# CH32V307VCT6.net
KiCad netlist of a schematic drawn in EasyEDA Pro
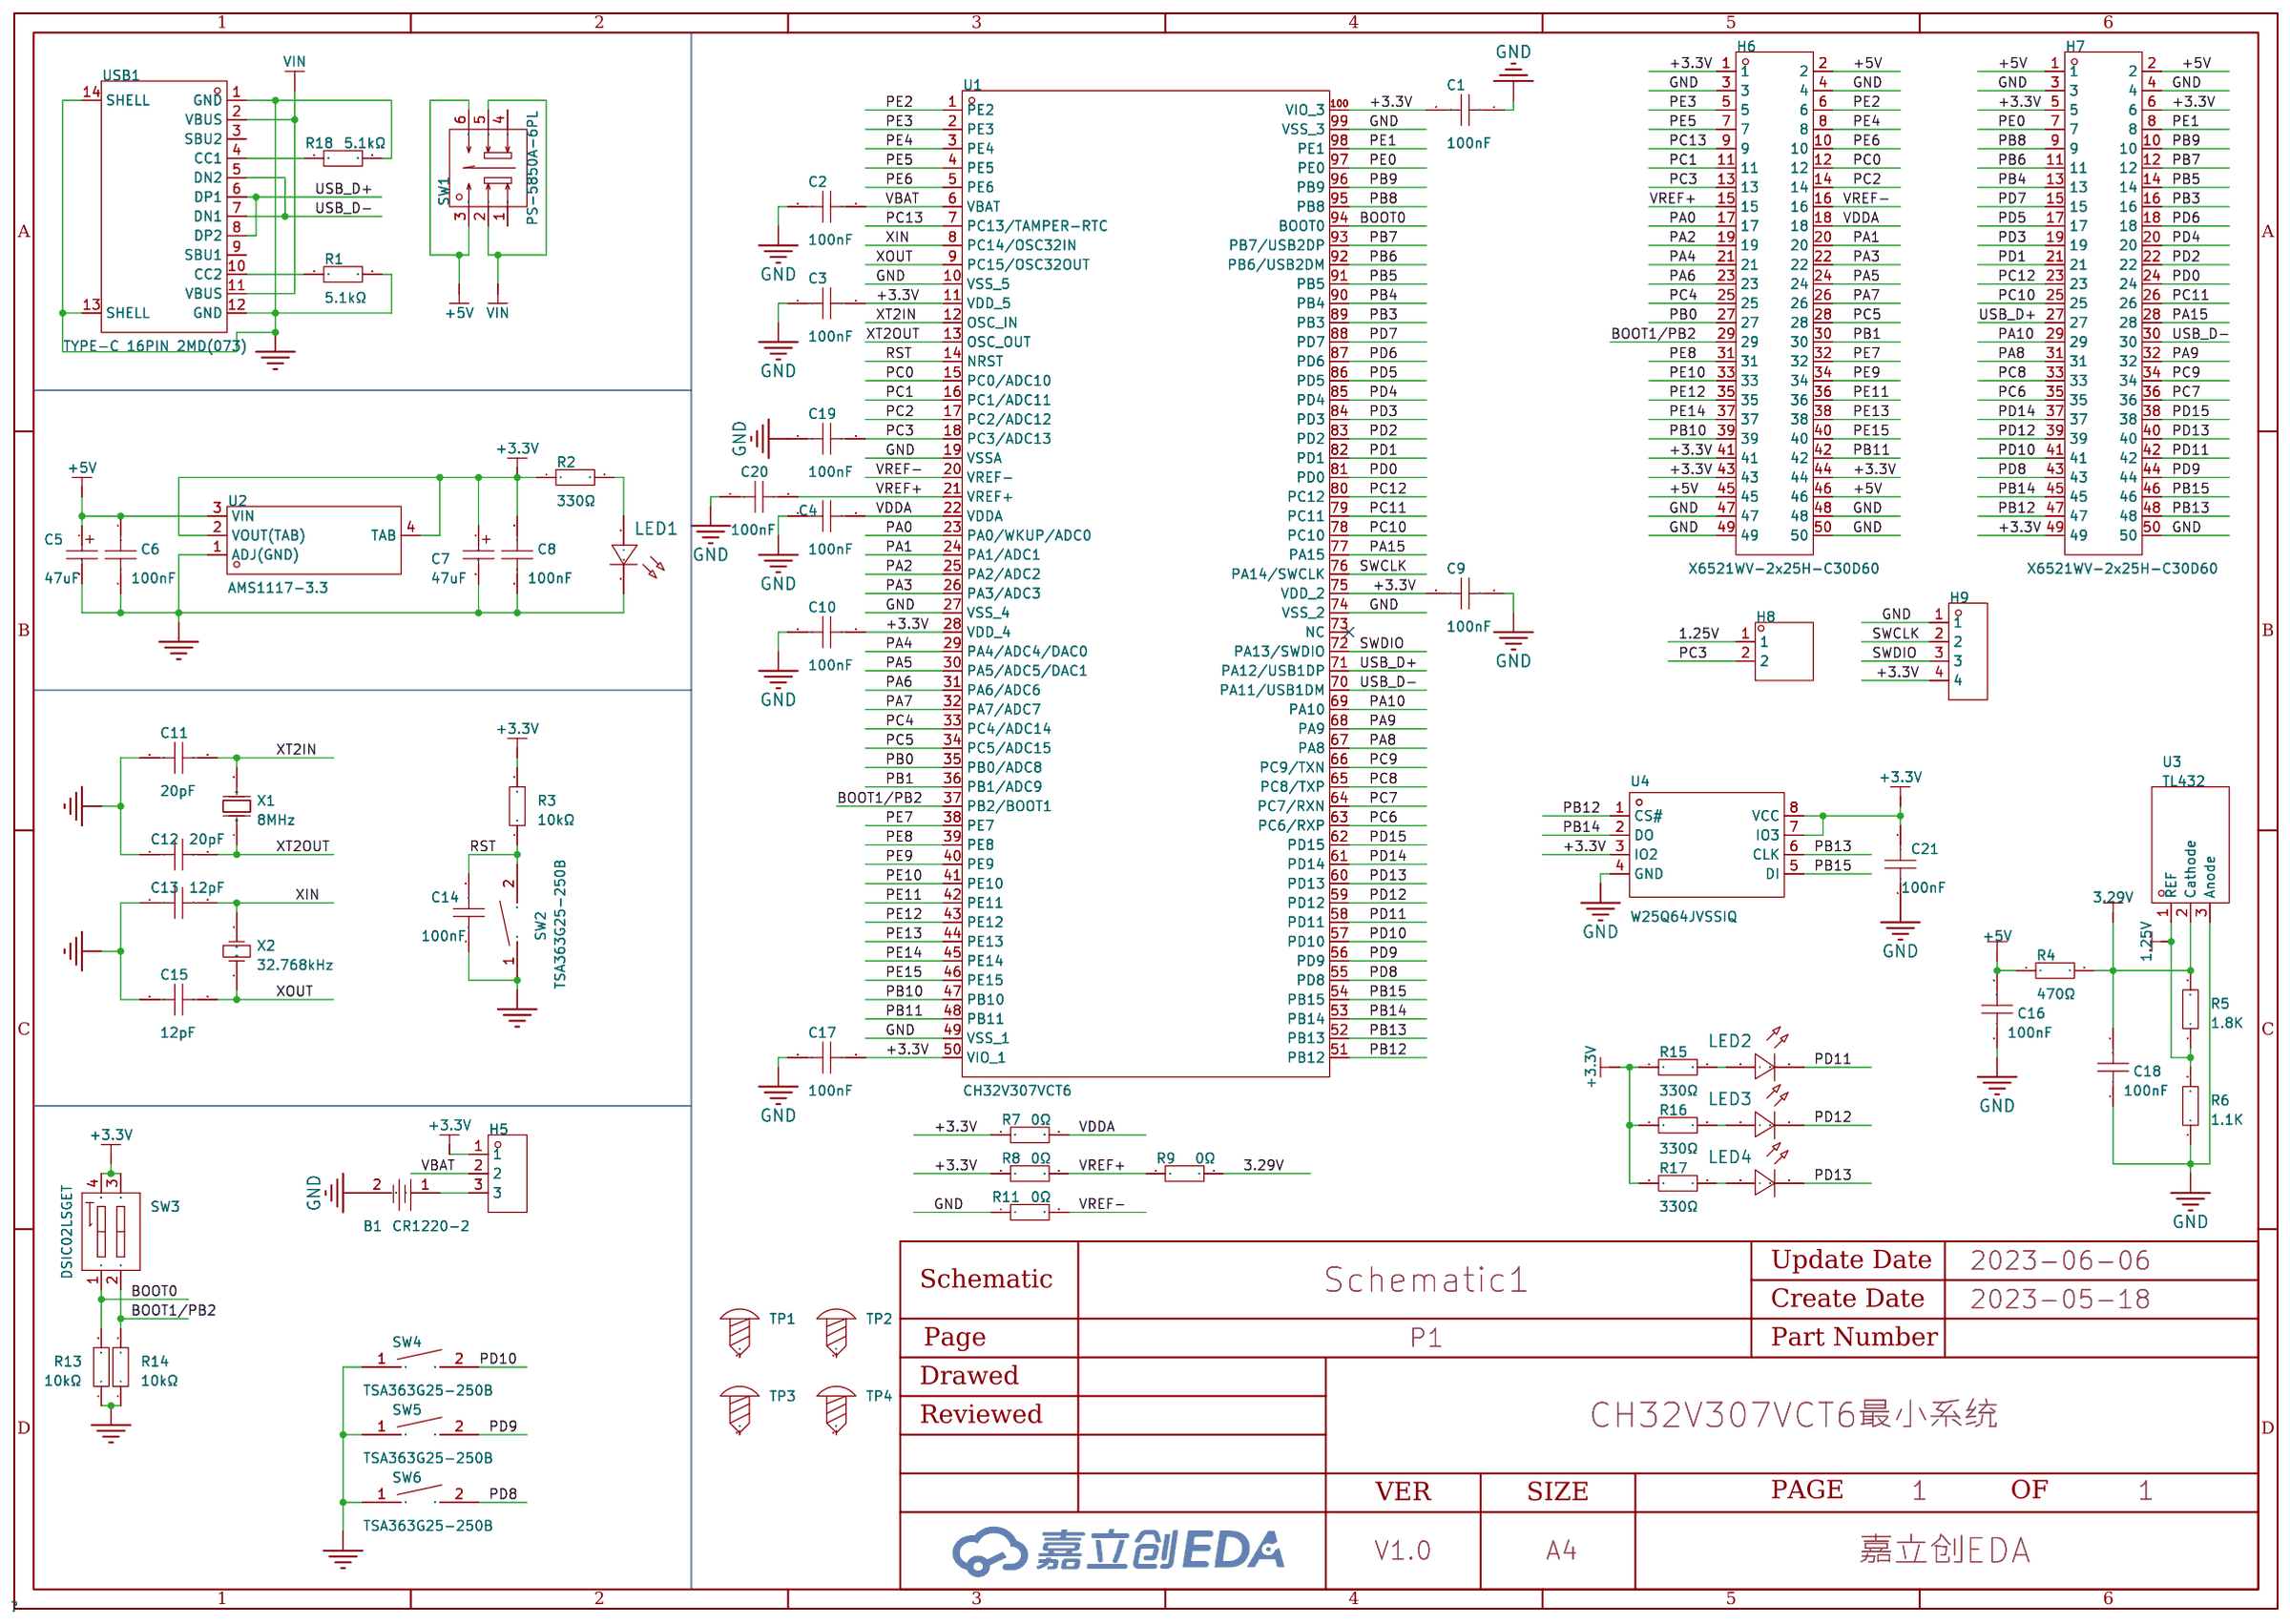
[diagram p0: schematic sheet]

(export (version "E")
  (design (tool "Eeschema 10.0.6"))
  (components
    (comp (ref "B1")
      (value "CR1220-2")
      (footprint "easyedapro:BAT-SMD_CR1220-2")
      (description "连接器类型:电池底座;适用电池规格:CR1220;工作温度范围:-;")
      (fields (field (name "Manufacturer") "Q&J"))
      (libsource (lib "easyedapro") (part "CR1220-2"))
    )
    (comp (ref "C1")
      (value "100nF")
      (footprint "easyedapro:C0805")
      (libsource (lib "easyedapro") (part "CapAcitance"))
    )
    (comp (ref "C2")
      (value "100nF")
      (footprint "easyedapro:C0805")
      (libsource (lib "easyedapro") (part "CapAcitance"))
    )
    (comp (ref "C3")
      (value "100nF")
      (footprint "easyedapro:C0805")
      (libsource (lib "easyedapro") (part "CapAcitance"))
    )
    (comp (ref "C4")
      (value "100nF")
      (footprint "easyedapro:C0805")
      (libsource (lib "easyedapro") (part "CapAcitance"))
    )
    (comp (ref "C5")
      (value "47uF")
      (footprint "easyedapro:CASE-B_3528")
      (description "容值:47uF;精度:±10%;额定电压:10V;等效串联电阻:1Ω@100kHz;工作温度:-55°C~+125°C;")
      (fields (field (name "Manufacturer Part") "TAJB476K010RNJ") (field (name "Manufacturer") "Kyocera AVX"))
      (libsource (lib "easyedapro") (part "TAJB476K010RNJ"))
    )
    (comp (ref "C6")
      (value "100nF")
      (footprint "easyedapro:C0805")
      (fields
        (field (name "Manufacturer Part") "CL21B104KBCNNNC")
        (field (name "Manufacturer") "SAMSUNG(三星)")
      )
      (libsource (lib "easyedapro") (part "CapAcitance"))
    )
    (comp (ref "C7")
      (value "47uF")
      (footprint "easyedapro:CASE-B_3528")
      (description "容值:47uF;精度:±10%;额定电压:10V;等效串联电阻:1Ω@100kHz;工作温度:-55°C~+125°C;")
      (fields (field (name "Manufacturer Part") "TAJB476K010RNJ") (field (name "Manufacturer") "Kyocera AVX"))
      (libsource (lib "easyedapro") (part "TAJB476K010RNJ"))
    )
    (comp (ref "C8")
      (value "100nF")
      (footprint "easyedapro:C0805")
      (fields
        (field (name "Manufacturer Part") "CL21B104KBCNNNC")
        (field (name "Manufacturer") "SAMSUNG(三星)")
      )
      (libsource (lib "easyedapro") (part "CapAcitance"))
    )
    (comp (ref "C9")
      (value "100nF")
      (footprint "easyedapro:C0805")
      (libsource (lib "easyedapro") (part "CapAcitance"))
    )
    (comp (ref "C10")
      (value "100nF")
      (footprint "easyedapro:C0805")
      (libsource (lib "easyedapro") (part "CapAcitance"))
    )
    (comp (ref "C11")
      (value "20pF")
      (footprint "easyedapro:C0805")
      (fields (field (name "Manufacturer Part") "0805CG200J500NT") (field (name "Manufacturer") "FH(风华)"))
      (libsource (lib "easyedapro") (part "CapAcitance"))
    )
    (comp (ref "C12")
      (value "20pF")
      (footprint "easyedapro:C0805")
      (fields (field (name "Manufacturer Part") "0805CG200J500NT") (field (name "Manufacturer") "FH(风华)"))
      (libsource (lib "easyedapro") (part "CapAcitance"))
    )
    (comp (ref "C13")
      (value "12pF")
      (footprint "easyedapro:C0805")
      (fields (field (name "Manufacturer Part") "0805CG120J500NT") (field (name "Manufacturer") "FH(风华)"))
      (libsource (lib "easyedapro") (part "CapAcitance"))
    )
    (comp (ref "C14")
      (value "100nF")
      (footprint "easyedapro:C0805")
      (fields
        (field (name "Manufacturer Part") "CL21B104KBCNNNC")
        (field (name "Manufacturer") "SAMSUNG(三星)")
      )
      (libsource (lib "easyedapro") (part "CapAcitance"))
    )
    (comp (ref "C15")
      (value "12pF")
      (footprint "easyedapro:C0805")
      (fields (field (name "Manufacturer Part") "0805CG120J500NT") (field (name "Manufacturer") "FH(风华)"))
      (libsource (lib "easyedapro") (part "CapAcitance"))
    )
    (comp (ref "C16")
      (value "100nF")
      (footprint "easyedapro:C0805")
      (libsource (lib "easyedapro") (part "CapAcitance"))
    )
    (comp (ref "C17")
      (value "100nF")
      (footprint "easyedapro:C0805")
      (libsource (lib "easyedapro") (part "CapAcitance"))
    )
    (comp (ref "C18")
      (value "100nF")
      (footprint "easyedapro:C0805")
      (libsource (lib "easyedapro") (part "CapAcitance"))
    )
    (comp (ref "C19")
      (value "100nF")
      (footprint "easyedapro:C0805")
      (libsource (lib "easyedapro") (part "CapAcitance"))
    )
    (comp (ref "C20")
      (value "100nF")
      (footprint "easyedapro:C0805")
      (libsource (lib "easyedapro") (part "CapAcitance"))
    )
    (comp (ref "C21")
      (value "100nF")
      (footprint "easyedapro:C0805")
      (libsource (lib "easyedapro") (part "CapAcitance"))
    )
    (comp (ref "H5")
      (value "~")
      (footprint "easyedapro:HDR-TH_3P-P2.54-V-M")
      (libsource (lib "easyedapro") (part "PZ254V-11-03P_C2937625"))
    )
    (comp (ref "H6")
      (value "X6521WV-2x25H-C30D60")
      (footprint "easyedapro:HDR-TH_50P-2.54-V-M-R2-C25-S2.54")
      (fields (field (name "Manufacturer") "XKB Connectivity(中国星坤)"))
      (libsource (lib "easyedapro") (part "X6521WV-2×25H-C30D60"))
    )
    (comp (ref "H7")
      (value "X6521WV-2x25H-C30D60")
      (footprint "easyedapro:HDR-TH_50P-2.54-V-M-R2-C25-S2.54")
      (fields (field (name "Manufacturer") "XKB Connectivity(中国星坤)"))
      (libsource (lib "easyedapro") (part "X6521WV-2×25H-C30D60"))
    )
    (comp (ref "H8")
      (value "~")
      (footprint "easyedapro:HDR-TH_2P-P2.54-V-M-1")
      (libsource (lib "easyedapro") (part "210S-1*2P L=11.6MMGold-plated black"))
    )
    (comp (ref "H9")
      (value "~")
      (footprint "easyedapro:HDR-TH_4P-P2.54-V-M")
      (libsource (lib "easyedapro") (part "PZ254V-11-04P"))
    )
    (comp (ref "LED1")
      (value "NCD0805R1")
      (fields (field (name "Manufacturer") "国星光电"))
      (libsource (lib "easyedapro") (part "LED_R"))
    )
    (comp (ref "LED2")
      (value "NCD0805R1")
      (fields (field (name "Manufacturer") "国星光电"))
      (libsource (lib "easyedapro") (part "LED_R"))
    )
    (comp (ref "LED3")
      (value "NCD0805R1")
      (fields (field (name "Manufacturer") "国星光电"))
      (libsource (lib "easyedapro") (part "LED_R"))
    )
    (comp (ref "LED4")
      (value "NCD0805R1")
      (fields (field (name "Manufacturer") "国星光电"))
      (libsource (lib "easyedapro") (part "LED_R"))
    )
    (comp (ref "R1")
      (value "5.1kΩ")
      (footprint "easyedapro:R0805")
      (fields
        (field (name "Manufacturer Part") "0805W8F5101T5E")
        (field (name "Manufacturer") "UNI-ROYAL(厚声)")
      )
      (libsource (lib "easyedapro") (part "电阻"))
    )
    (comp (ref "R2") (value "330Ω") (footprint "easyedapro:R0805") (libsource (lib "easyedapro") (part "电阻")))
    (comp (ref "R3")
      (value "10kΩ")
      (footprint "easyedapro:R0805")
      (fields
        (field (name "Manufacturer Part") "0805W8F1002T5E")
        (field (name "Manufacturer") "UNI-ROYAL(厚声)")
      )
      (libsource (lib "easyedapro") (part "电阻"))
    )
    (comp (ref "R4") (value "470Ω") (footprint "easyedapro:R0805") (libsource (lib "easyedapro") (part "电阻")))
    (comp (ref "R5") (value "1.8K") (footprint "easyedapro:R0805") (libsource (lib "easyedapro") (part "电阻")))
    (comp (ref "R6") (value "1.1K") (footprint "easyedapro:R0805") (libsource (lib "easyedapro") (part "电阻")))
    (comp (ref "R7") (value "0Ω") (footprint "easyedapro:R0805") (libsource (lib "easyedapro") (part "电阻")))
    (comp (ref "R8") (value "0Ω") (footprint "easyedapro:R0805") (libsource (lib "easyedapro") (part "电阻")))
    (comp (ref "R9") (value "0Ω") (footprint "easyedapro:R0805") (libsource (lib "easyedapro") (part "电阻")))
    (comp (ref "R11") (value "0Ω") (footprint "easyedapro:R0805") (libsource (lib "easyedapro") (part "电阻")))
    (comp (ref "R13")
      (value "10kΩ")
      (footprint "easyedapro:R0805")
      (fields
        (field (name "Manufacturer Part") "0805W8F1002T5E")
        (field (name "Manufacturer") "UNI-ROYAL(厚声)")
      )
      (libsource (lib "easyedapro") (part "电阻"))
    )
    (comp (ref "R14")
      (value "10kΩ")
      (footprint "easyedapro:R0805")
      (fields
        (field (name "Manufacturer Part") "0805W8F1002T5E")
        (field (name "Manufacturer") "UNI-ROYAL(厚声)")
      )
      (libsource (lib "easyedapro") (part "电阻"))
    )
    (comp (ref "R15")
      (value "330Ω")
      (footprint "easyedapro:R0805")
      (libsource (lib "easyedapro") (part "电阻"))
    )
    (comp (ref "R16")
      (value "330Ω")
      (footprint "easyedapro:R0805")
      (libsource (lib "easyedapro") (part "电阻"))
    )
    (comp (ref "R17")
      (value "330Ω")
      (footprint "easyedapro:R0805")
      (libsource (lib "easyedapro") (part "电阻"))
    )
    (comp (ref "R18")
      (value "5.1kΩ")
      (footprint "easyedapro:R0805")
      (fields
        (field (name "Manufacturer Part") "0805W8F5101T5E")
        (field (name "Manufacturer") "UNI-ROYAL(厚声)")
      )
      (libsource (lib "easyedapro") (part "电阻"))
    )
    (comp (ref "SW1")
      (value "PS-5850A-6PL")
      (footprint "easyedapro:SW-TH_6P-L5.8-W5.8-P2.00-LS4.5-BL")
      (description "5.8自锁按键开关 高头 耐高温")
      (fields (field (name "Manufacturer") "G-Switch(品赞)"))
      (libsource (lib "easyedapro") (part "PS-5850A-6PL"))
    )
    (comp (ref "SW2")
      (value "TSA363G25-250B")
      (footprint "easyedapro:SW-SMD_L6.1-W3.6-LS8.0")
      (description "触点电流:50mA;额定电压(DC):12V;电路结构:单刀单掷;按钮作用方向:顶部触动;致动器样式:矩形按钮;照明颜色:-;开关长度:6.05mm;开关宽度:3.6mm;开关高度:2.5mm;")
      (fields (field (name "Manufacturer") "BRIGHT(博瑞泰)"))
      (libsource (lib "easyedapro") (part "TSA363G25-250B"))
    )
    (comp (ref "SW3")
      (value "DSIC02LSGET")
      (footprint "easyedapro:SW-SMD_4P-L6.0-W5.1-P2.54-LS9.3-BL")
      (description "类型:平拨，凸起式;电路结构:单刀单掷;开关位数:2;引脚间距:2.54mm;颜色:黑色;")
      (fields (field (name "Manufacturer") "YE"))
      (libsource (lib "easyedapro") (part "DSIC02LSGET"))
    )
    (comp (ref "SW4")
      (value "TSA363G25-250B")
      (footprint "easyedapro:SW-SMD_L6.1-W3.6-LS8.0")
      (description "触点电流:50mA;额定电压(DC):12V;电路结构:单刀单掷;按钮作用方向:顶部触动;致动器样式:矩形按钮;照明颜色:-;开关长度:6.05mm;开关宽度:3.6mm;开关高度:2.5mm;")
      (fields (field (name "Manufacturer") "BRIGHT(博瑞泰)"))
      (libsource (lib "easyedapro") (part "TSA363G25-250B"))
    )
    (comp (ref "SW5")
      (value "TSA363G25-250B")
      (footprint "easyedapro:SW-SMD_L6.1-W3.6-LS8.0")
      (description "触点电流:50mA;额定电压(DC):12V;电路结构:单刀单掷;按钮作用方向:顶部触动;致动器样式:矩形按钮;照明颜色:-;开关长度:6.05mm;开关宽度:3.6mm;开关高度:2.5mm;")
      (fields (field (name "Manufacturer") "BRIGHT(博瑞泰)"))
      (libsource (lib "easyedapro") (part "TSA363G25-250B"))
    )
    (comp (ref "SW6")
      (value "TSA363G25-250B")
      (footprint "easyedapro:SW-SMD_L6.1-W3.6-LS8.0")
      (description "触点电流:50mA;额定电压(DC):12V;电路结构:单刀单掷;按钮作用方向:顶部触动;致动器样式:矩形按钮;照明颜色:-;开关长度:6.05mm;开关宽度:3.6mm;开关高度:2.5mm;")
      (fields (field (name "Manufacturer") "BRIGHT(博瑞泰)"))
      (libsource (lib "easyedapro") (part "TSA363G25-250B"))
    )
    (comp (ref "TP1") (value "~") (footprint "easyedapro:M3螺丝") (libsource (lib "easyedapro") (part "螺丝孔")))
    (comp (ref "TP2") (value "~") (footprint "easyedapro:M3螺丝") (libsource (lib "easyedapro") (part "螺丝孔")))
    (comp (ref "TP3") (value "~") (footprint "easyedapro:M3螺丝") (libsource (lib "easyedapro") (part "螺丝孔")))
    (comp (ref "TP4") (value "~") (footprint "easyedapro:M3螺丝") (libsource (lib "easyedapro") (part "螺丝孔")))
    (comp (ref "U1")
      (value "CH32V307VCT6")
      (footprint "easyedapro:LQFP-100_L14.0-W14.0-P0.50-LS16.0-BL")
      (fields (field (name "Manufacturer") "WCH(南京沁恒)"))
      (libsource (lib "easyedapro") (part "CH32V307VCT6"))
    )
    (comp (ref "U2")
      (value "AMS1117-3.3")
      (footprint "easyedapro:SOT-223-4_L6.5-W3.5-P2.30-LS7.0-BR")
      (description "输出类型:固定;输出极性:正;输出通道数:1;最大输入电压:18V;输出电压:3.3V;压差:1.3V@(1A);输出电流:1A;电源纹波抑制比(PSRR):60dB@(120Hz);")
      (fields (field (name "Manufacturer") "UMW(广东友台半导体)"))
      (libsource (lib "easyedapro") (part "AMS1117-3.3_C347222"))
    )
    (comp (ref "U3")
      (value "TL432")
      (footprint "easyedapro:SOT-23-3_L2.9-W1.3-P1.90-LS2.4-BR")
      (fields (field (name "Manufacturer") "HXY MOSFET(华轩阳电子)"))
      (libsource (lib "easyedapro") (part "TL432_C5184435"))
    )
    (comp (ref "U4")
      (value "W25Q64JVSSIQ")
      (footprint "easyedapro:SOP-8_L5.3-W5.3-P1.27-LS8.0-BL")
      (description "64M-bit/8M-byte FLASH芯片,SPI接口 133MHz(266/532MHz Dual/Quad-SPI) 比W25Q64FVSSIG更高速度")
      (fields (field (name "Manufacturer") "WINBOND(华邦)"))
      (libsource (lib "easyedapro") (part "W25Q64JVSSIQ"))
    )
    (comp (ref "USB1")
      (value "TYPE-C 16PIN 2MD(073)")
      (footprint "easyedapro:USB-C-SMD_TYPE-C-6PIN-2MD-073")
      (description "连接器类型:Type-C;标准:-;公母:母座;触点数量:16;端口数量:1;安装方式:卧贴;额定电流 - 电源:5A;工作温度范围:-25°C~+85°C;")
      (fields (field (name "Manufacturer") "SHOU HAN(首韩)"))
      (libsource (lib "easyedapro") (part "TYPE-C 16PIN 2MD(073)"))
    )
    (comp (ref "X1")
      (value "8MHz")
      (footprint "easyedapro:CRYSTAL-SMD_L5.0-W3.2")
      (description "频率:8MHz;频率公差:±10ppm;负载电容:20pF;")
      (fields (field (name "Manufacturer Part") "X50328MSB2GI") (field (name "Manufacturer") "YXC(扬兴晶振)"))
      (libsource (lib "easyedapro") (part "X50328MSB2GI"))
    )
    (comp (ref "X2")
      (value "32.768kHz")
      (footprint "easyedapro:OSC-TH_BD3.1-P0.8-D0.3")
      (description "频率:32.768kHz;频率公差:±10ppm;负载电容:12.5pF;")
      (fields (field (name "Manufacturer Part") "X308032768KGB2SC") (field (name "Manufacturer") "YXC(扬兴晶振)"))
      (libsource (lib "easyedapro") (part "X308032768KGB2SC"))
    )
  )
  (nets
    (net (code "1") (name "+3.3V") (class "Default")
      (node (ref "C1") (pin "2") (pinfunction "2_2") (pintype "input"))
      (node (ref "C10") (pin "2") (pinfunction "2_2") (pintype "input"))
      (node (ref "C17") (pin "2") (pinfunction "2_2") (pintype "input"))
      (node (ref "C21") (pin "2") (pinfunction "2_2") (pintype "input"))
      (node (ref "C3") (pin "2") (pinfunction "2_2") (pintype "input"))
      (node (ref "C7") (pin "1") (pinfunction "1_1") (pintype "input"))
      (node (ref "C8") (pin "2") (pinfunction "2_2") (pintype "input"))
      (node (ref "C9") (pin "2") (pinfunction "2_2") (pintype "input"))
      (node (ref "H5") (pin "1") (pinfunction "1_1") (pintype "input"))
      (node (ref "H6") (pin "1") (pinfunction "1_1") (pintype "input"))
      (node (ref "H6") (pin "41") (pinfunction "41_41") (pintype "input"))
      (node (ref "H6") (pin "43") (pinfunction "43_43") (pintype "input"))
      (node (ref "H6") (pin "44") (pinfunction "44_44") (pintype "input"))
      (node (ref "H7") (pin "49") (pinfunction "49_49") (pintype "input"))
      (node (ref "H7") (pin "5") (pinfunction "5_5") (pintype "input"))
      (node (ref "H7") (pin "6") (pinfunction "6_6") (pintype "input"))
      (node (ref "H9") (pin "4") (pinfunction "4_4") (pintype "input"))
      (node (ref "R15") (pin "1") (pinfunction "1_1") (pintype "input"))
      (node (ref "R16") (pin "1") (pinfunction "1_1") (pintype "input"))
      (node (ref "R17") (pin "1") (pinfunction "1_1") (pintype "input"))
      (node (ref "R2") (pin "1") (pinfunction "1_1") (pintype "input"))
      (node (ref "R3") (pin "2") (pinfunction "2_2") (pintype "input"))
      (node (ref "R7") (pin "1") (pinfunction "1_1") (pintype "input"))
      (node (ref "R8") (pin "1") (pinfunction "1_1") (pintype "input"))
      (node (ref "SW3") (pin "3") (pinfunction "B2_3") (pintype "input"))
      (node (ref "SW3") (pin "4") (pinfunction "B1_4") (pintype "input"))
      (node (ref "U1") (pin "100") (pinfunction "VIO_3_100") (pintype "input"))
      (node (ref "U1") (pin "11") (pinfunction "VDD_5_11") (pintype "input"))
      (node (ref "U1") (pin "28") (pinfunction "VDD_4_28") (pintype "input"))
      (node (ref "U1") (pin "50") (pinfunction "VIO_1_50") (pintype "input"))
      (node (ref "U1") (pin "75") (pinfunction "VDD_2_75") (pintype "input"))
      (node (ref "U2") (pin "2") (pinfunction "VOUT(TAB)_2") (pintype "input"))
      (node (ref "U2") (pin "4") (pinfunction "TAB_4") (pintype "input"))
      (node (ref "U4") (pin "3") (pinfunction "IO2_3") (pintype "input"))
      (node (ref "U4") (pin "7") (pinfunction "IO3_7") (pintype "input"))
      (node (ref "U4") (pin "8") (pinfunction "VCC_8") (pintype "input"))
    )
    (net (code "2") (name "+5V") (class "Default")
      (node (ref "C16") (pin "2") (pinfunction "2_2") (pintype "input"))
      (node (ref "C5") (pin "1") (pinfunction "1_1") (pintype "input"))
      (node (ref "C6") (pin "2") (pinfunction "2_2") (pintype "input"))
      (node (ref "H6") (pin "2") (pinfunction "2_2") (pintype "input"))
      (node (ref "H6") (pin "45") (pinfunction "45_45") (pintype "input"))
      (node (ref "H6") (pin "46") (pinfunction "46_46") (pintype "input"))
      (node (ref "H7") (pin "1") (pinfunction "1_1") (pintype "input"))
      (node (ref "H7") (pin "2") (pinfunction "2_2") (pintype "input"))
      (node (ref "R4") (pin "1") (pinfunction "1_1") (pintype "input"))
      (node (ref "SW1") (pin "3") (pinfunction "3_3") (pintype "input"))
      (node (ref "SW1") (pin "6") (pinfunction "6_6") (pintype "input"))
      (node (ref "U2") (pin "3") (pinfunction "VIN_3") (pintype "input"))
    )
    (net (code "3") (name "/BOOT0") (class "Default")
      (node (ref "R13") (pin "2") (pinfunction "2_2") (pintype "input"))
      (node (ref "SW3") (pin "1") (pinfunction "A1_1") (pintype "input"))
      (node (ref "U1") (pin "94") (pinfunction "BOOT0_94") (pintype "input"))
    )
    (net (code "4") (name "/BOOT1{slash}PB2") (class "Default")
      (node (ref "H6") (pin "29") (pinfunction "29_29") (pintype "input"))
      (node (ref "R14") (pin "2") (pinfunction "2_2") (pintype "input"))
      (node (ref "SW3") (pin "2") (pinfunction "A2_2") (pintype "input"))
      (node (ref "U1") (pin "37") (pinfunction "PB2/BOOT1_37") (pintype "input"))
    )
    (net (code "5") (name "/PA0") (class "Default")
      (node (ref "H6") (pin "17") (pinfunction "17_17") (pintype "input"))
      (node (ref "U1") (pin "23") (pinfunction "PA0/WKUP/ADC0_23") (pintype "input"))
    )
    (net (code "6") (name "/PA1") (class "Default")
      (node (ref "H6") (pin "20") (pinfunction "20_20") (pintype "input"))
      (node (ref "U1") (pin "24") (pinfunction "PA1/ADC1_24") (pintype "input"))
    )
    (net (code "7") (name "/PA2") (class "Default")
      (node (ref "H6") (pin "19") (pinfunction "19_19") (pintype "input"))
      (node (ref "U1") (pin "25") (pinfunction "PA2/ADC2_25") (pintype "input"))
    )
    (net (code "8") (name "/PA3") (class "Default")
      (node (ref "H6") (pin "22") (pinfunction "22_22") (pintype "input"))
      (node (ref "U1") (pin "26") (pinfunction "PA3/ADC3_26") (pintype "input"))
    )
    (net (code "9") (name "/PA4") (class "Default")
      (node (ref "H6") (pin "21") (pinfunction "21_21") (pintype "input"))
      (node (ref "U1") (pin "29") (pinfunction "PA4/ADC4/DAC0_29") (pintype "input"))
    )
    (net (code "10") (name "/PA5") (class "Default")
      (node (ref "H6") (pin "24") (pinfunction "24_24") (pintype "input"))
      (node (ref "U1") (pin "30") (pinfunction "PA5/ADC5/DAC1_30") (pintype "input"))
    )
    (net (code "11") (name "/PA6") (class "Default")
      (node (ref "H6") (pin "23") (pinfunction "23_23") (pintype "input"))
      (node (ref "U1") (pin "31") (pinfunction "PA6/ADC6_31") (pintype "input"))
    )
    (net (code "12") (name "/PA7") (class "Default")
      (node (ref "H6") (pin "26") (pinfunction "26_26") (pintype "input"))
      (node (ref "U1") (pin "32") (pinfunction "PA7/ADC7_32") (pintype "input"))
    )
    (net (code "13") (name "/PA8") (class "Default")
      (node (ref "H7") (pin "31") (pinfunction "31_31") (pintype "input"))
      (node (ref "U1") (pin "67") (pinfunction "PA8_67") (pintype "input"))
    )
    (net (code "14") (name "/PA9") (class "Default")
      (node (ref "H7") (pin "32") (pinfunction "32_32") (pintype "input"))
      (node (ref "U1") (pin "68") (pinfunction "PA9_68") (pintype "input"))
    )
    (net (code "15") (name "/PA10") (class "Default")
      (node (ref "H7") (pin "29") (pinfunction "29_29") (pintype "input"))
      (node (ref "U1") (pin "69") (pinfunction "PA10_69") (pintype "input"))
    )
    (net (code "16") (name "/PA15") (class "Default")
      (node (ref "H7") (pin "28") (pinfunction "28_28") (pintype "input"))
      (node (ref "U1") (pin "77") (pinfunction "PA15_77") (pintype "input"))
    )
    (net (code "17") (name "/PB0") (class "Default")
      (node (ref "H6") (pin "27") (pinfunction "27_27") (pintype "input"))
      (node (ref "U1") (pin "35") (pinfunction "PB0/ADC8_35") (pintype "input"))
    )
    (net (code "18") (name "/PB1") (class "Default")
      (node (ref "H6") (pin "30") (pinfunction "30_30") (pintype "input"))
      (node (ref "U1") (pin "36") (pinfunction "PB1/ADC9_36") (pintype "input"))
    )
    (net (code "19") (name "/PB3") (class "Default")
      (node (ref "H7") (pin "16") (pinfunction "16_16") (pintype "input"))
      (node (ref "U1") (pin "89") (pinfunction "PB3_89") (pintype "input"))
    )
    (net (code "20") (name "/PB4") (class "Default")
      (node (ref "H7") (pin "13") (pinfunction "13_13") (pintype "input"))
      (node (ref "U1") (pin "90") (pinfunction "PB4_90") (pintype "input"))
    )
    (net (code "21") (name "/PB5") (class "Default")
      (node (ref "H7") (pin "14") (pinfunction "14_14") (pintype "input"))
      (node (ref "U1") (pin "91") (pinfunction "PB5_91") (pintype "input"))
    )
    (net (code "22") (name "/PB6") (class "Default")
      (node (ref "H7") (pin "11") (pinfunction "11_11") (pintype "input"))
      (node (ref "U1") (pin "92") (pinfunction "PB6/USB2DM_92") (pintype "input"))
    )
    (net (code "23") (name "/PB7") (class "Default")
      (node (ref "H7") (pin "12") (pinfunction "12_12") (pintype "input"))
      (node (ref "U1") (pin "93") (pinfunction "PB7/USB2DP_93") (pintype "input"))
    )
    (net (code "24") (name "/PB8") (class "Default")
      (node (ref "H7") (pin "9") (pinfunction "9_9") (pintype "input"))
      (node (ref "U1") (pin "95") (pinfunction "PB8_95") (pintype "input"))
    )
    (net (code "25") (name "/PB9") (class "Default")
      (node (ref "H7") (pin "10") (pinfunction "10_10") (pintype "input"))
      (node (ref "U1") (pin "96") (pinfunction "PB9_96") (pintype "input"))
    )
    (net (code "26") (name "/PB10") (class "Default")
      (node (ref "H6") (pin "39") (pinfunction "39_39") (pintype "input"))
      (node (ref "U1") (pin "47") (pinfunction "PB10_47") (pintype "input"))
    )
    (net (code "27") (name "/PB11") (class "Default")
      (node (ref "H6") (pin "42") (pinfunction "42_42") (pintype "input"))
      (node (ref "U1") (pin "48") (pinfunction "PB11_48") (pintype "input"))
    )
    (net (code "28") (name "/PB12") (class "Default")
      (node (ref "H7") (pin "47") (pinfunction "47_47") (pintype "input"))
      (node (ref "U1") (pin "51") (pinfunction "PB12_51") (pintype "input"))
      (node (ref "U4") (pin "1") (pinfunction "CS#_1") (pintype "input"))
    )
    (net (code "29") (name "/PB13") (class "Default")
      (node (ref "H7") (pin "48") (pinfunction "48_48") (pintype "input"))
      (node (ref "U1") (pin "52") (pinfunction "PB13_52") (pintype "input"))
      (node (ref "U4") (pin "6") (pinfunction "CLK_6") (pintype "input"))
    )
    (net (code "30") (name "/PB14") (class "Default")
      (node (ref "H7") (pin "45") (pinfunction "45_45") (pintype "input"))
      (node (ref "U1") (pin "53") (pinfunction "PB14_53") (pintype "input"))
      (node (ref "U4") (pin "2") (pinfunction "DO_2") (pintype "input"))
    )
    (net (code "31") (name "/PB15") (class "Default")
      (node (ref "H7") (pin "46") (pinfunction "46_46") (pintype "input"))
      (node (ref "U1") (pin "54") (pinfunction "PB15_54") (pintype "input"))
      (node (ref "U4") (pin "5") (pinfunction "DI_5") (pintype "input"))
    )
    (net (code "32") (name "/PC0") (class "Default")
      (node (ref "H6") (pin "12") (pinfunction "12_12") (pintype "input"))
      (node (ref "U1") (pin "15") (pinfunction "PC0/ADC10_15") (pintype "input"))
    )
    (net (code "33") (name "/PC1") (class "Default")
      (node (ref "H6") (pin "11") (pinfunction "11_11") (pintype "input"))
      (node (ref "U1") (pin "16") (pinfunction "PC1/ADC11_16") (pintype "input"))
    )
    (net (code "34") (name "/PC2") (class "Default")
      (node (ref "H6") (pin "14") (pinfunction "14_14") (pintype "input"))
      (node (ref "U1") (pin "17") (pinfunction "PC2/ADC12_17") (pintype "input"))
    )
    (net (code "35") (name "/PC3") (class "Default")
      (node (ref "C19") (pin "2") (pinfunction "2_2") (pintype "input"))
      (node (ref "H6") (pin "13") (pinfunction "13_13") (pintype "input"))
      (node (ref "H8") (pin "2") (pinfunction "2_2") (pintype "input"))
      (node (ref "U1") (pin "18") (pinfunction "PC3/ADC13_18") (pintype "input"))
    )
    (net (code "36") (name "/PC4") (class "Default")
      (node (ref "H6") (pin "25") (pinfunction "25_25") (pintype "input"))
      (node (ref "U1") (pin "33") (pinfunction "PC4/ADC14_33") (pintype "input"))
    )
    (net (code "37") (name "/PC5") (class "Default")
      (node (ref "H6") (pin "28") (pinfunction "28_28") (pintype "input"))
      (node (ref "U1") (pin "34") (pinfunction "PC5/ADC15_34") (pintype "input"))
    )
    (net (code "38") (name "/PC6") (class "Default")
      (node (ref "H7") (pin "35") (pinfunction "35_35") (pintype "input"))
      (node (ref "U1") (pin "63") (pinfunction "PC6/RXP_63") (pintype "input"))
    )
    (net (code "39") (name "/PC7") (class "Default")
      (node (ref "H7") (pin "36") (pinfunction "36_36") (pintype "input"))
      (node (ref "U1") (pin "64") (pinfunction "PC7/RXN_64") (pintype "input"))
    )
    (net (code "40") (name "/PC8") (class "Default")
      (node (ref "H7") (pin "33") (pinfunction "33_33") (pintype "input"))
      (node (ref "U1") (pin "65") (pinfunction "PC8/TXP_65") (pintype "input"))
    )
    (net (code "41") (name "/PC9") (class "Default")
      (node (ref "H7") (pin "34") (pinfunction "34_34") (pintype "input"))
      (node (ref "U1") (pin "66") (pinfunction "PC9/TXN_66") (pintype "input"))
    )
    (net (code "42") (name "/PC10") (class "Default")
      (node (ref "H7") (pin "25") (pinfunction "25_25") (pintype "input"))
      (node (ref "U1") (pin "78") (pinfunction "PC10_78") (pintype "input"))
    )
    (net (code "43") (name "/PC11") (class "Default")
      (node (ref "H7") (pin "26") (pinfunction "26_26") (pintype "input"))
      (node (ref "U1") (pin "79") (pinfunction "PC11_79") (pintype "input"))
    )
    (net (code "44") (name "/PC12") (class "Default")
      (node (ref "H7") (pin "23") (pinfunction "23_23") (pintype "input"))
      (node (ref "U1") (pin "80") (pinfunction "PC12_80") (pintype "input"))
    )
    (net (code "45") (name "/PC13") (class "Default")
      (node (ref "H6") (pin "9") (pinfunction "9_9") (pintype "input"))
      (node (ref "U1") (pin "7") (pinfunction "PC13/TAMPER-RTC_7") (pintype "input"))
    )
    (net (code "46") (name "/PD0") (class "Default")
      (node (ref "H7") (pin "24") (pinfunction "24_24") (pintype "input"))
      (node (ref "U1") (pin "81") (pinfunction "PD0_81") (pintype "input"))
    )
    (net (code "47") (name "/PD1") (class "Default")
      (node (ref "H7") (pin "21") (pinfunction "21_21") (pintype "input"))
      (node (ref "U1") (pin "82") (pinfunction "PD1_82") (pintype "input"))
    )
    (net (code "48") (name "/PD2") (class "Default")
      (node (ref "H7") (pin "22") (pinfunction "22_22") (pintype "input"))
      (node (ref "U1") (pin "83") (pinfunction "PD2_83") (pintype "input"))
    )
    (net (code "49") (name "/PD3") (class "Default")
      (node (ref "H7") (pin "19") (pinfunction "19_19") (pintype "input"))
      (node (ref "U1") (pin "84") (pinfunction "PD3_84") (pintype "input"))
    )
    (net (code "50") (name "/PD4") (class "Default")
      (node (ref "H7") (pin "20") (pinfunction "20_20") (pintype "input"))
      (node (ref "U1") (pin "85") (pinfunction "PD4_85") (pintype "input"))
    )
    (net (code "51") (name "/PD5") (class "Default")
      (node (ref "H7") (pin "17") (pinfunction "17_17") (pintype "input"))
      (node (ref "U1") (pin "86") (pinfunction "PD5_86") (pintype "input"))
    )
    (net (code "52") (name "/PD6") (class "Default")
      (node (ref "H7") (pin "18") (pinfunction "18_18") (pintype "input"))
      (node (ref "U1") (pin "87") (pinfunction "PD6_87") (pintype "input"))
    )
    (net (code "53") (name "/PD7") (class "Default")
      (node (ref "H7") (pin "15") (pinfunction "15_15") (pintype "input"))
      (node (ref "U1") (pin "88") (pinfunction "PD7_88") (pintype "input"))
    )
    (net (code "54") (name "/PD8") (class "Default")
      (node (ref "H7") (pin "43") (pinfunction "43_43") (pintype "input"))
      (node (ref "SW6") (pin "2") (pinfunction "2_2") (pintype "input"))
      (node (ref "U1") (pin "55") (pinfunction "PD8_55") (pintype "input"))
    )
    (net (code "55") (name "/PD9") (class "Default")
      (node (ref "H7") (pin "44") (pinfunction "44_44") (pintype "input"))
      (node (ref "SW5") (pin "2") (pinfunction "2_2") (pintype "input"))
      (node (ref "U1") (pin "56") (pinfunction "PD9_56") (pintype "input"))
    )
    (net (code "56") (name "/PD10") (class "Default")
      (node (ref "H7") (pin "41") (pinfunction "41_41") (pintype "input"))
      (node (ref "SW4") (pin "2") (pinfunction "2_2") (pintype "input"))
      (node (ref "U1") (pin "57") (pinfunction "PD10_57") (pintype "input"))
    )
    (net (code "57") (name "/PD11") (class "Default")
      (node (ref "H7") (pin "42") (pinfunction "42_42") (pintype "input"))
      (node (ref "LED2") (pin "1") (pinfunction "C_1") (pintype "input"))
      (node (ref "U1") (pin "58") (pinfunction "PD11_58") (pintype "input"))
    )
    (net (code "58") (name "/PD12") (class "Default")
      (node (ref "H7") (pin "39") (pinfunction "39_39") (pintype "input"))
      (node (ref "LED3") (pin "1") (pinfunction "C_1") (pintype "input"))
      (node (ref "U1") (pin "59") (pinfunction "PD12_59") (pintype "input"))
    )
    (net (code "59") (name "/PD13") (class "Default")
      (node (ref "H7") (pin "40") (pinfunction "40_40") (pintype "input"))
      (node (ref "LED4") (pin "1") (pinfunction "C_1") (pintype "input"))
      (node (ref "U1") (pin "60") (pinfunction "PD13_60") (pintype "input"))
    )
    (net (code "60") (name "/PD14") (class "Default")
      (node (ref "H7") (pin "37") (pinfunction "37_37") (pintype "input"))
      (node (ref "U1") (pin "61") (pinfunction "PD14_61") (pintype "input"))
    )
    (net (code "61") (name "/PD15") (class "Default")
      (node (ref "H7") (pin "38") (pinfunction "38_38") (pintype "input"))
      (node (ref "U1") (pin "62") (pinfunction "PD15_62") (pintype "input"))
    )
    (net (code "62") (name "/PE0") (class "Default")
      (node (ref "H7") (pin "7") (pinfunction "7_7") (pintype "input"))
      (node (ref "U1") (pin "97") (pinfunction "PE0_97") (pintype "input"))
    )
    (net (code "63") (name "/PE1") (class "Default")
      (node (ref "H7") (pin "8") (pinfunction "8_8") (pintype "input"))
      (node (ref "U1") (pin "98") (pinfunction "PE1_98") (pintype "input"))
    )
    (net (code "64") (name "/PE2") (class "Default")
      (node (ref "H6") (pin "6") (pinfunction "6_6") (pintype "input"))
      (node (ref "U1") (pin "1") (pinfunction "PE2_1") (pintype "input"))
    )
    (net (code "65") (name "/PE3") (class "Default")
      (node (ref "H6") (pin "5") (pinfunction "5_5") (pintype "input"))
      (node (ref "U1") (pin "2") (pinfunction "PE3_2") (pintype "input"))
    )
    (net (code "66") (name "/PE4") (class "Default")
      (node (ref "H6") (pin "8") (pinfunction "8_8") (pintype "input"))
      (node (ref "U1") (pin "3") (pinfunction "PE4_3") (pintype "input"))
    )
    (net (code "67") (name "/PE5") (class "Default")
      (node (ref "H6") (pin "7") (pinfunction "7_7") (pintype "input"))
      (node (ref "U1") (pin "4") (pinfunction "PE5_4") (pintype "input"))
    )
    (net (code "68") (name "/PE6") (class "Default")
      (node (ref "H6") (pin "10") (pinfunction "10_10") (pintype "input"))
      (node (ref "U1") (pin "5") (pinfunction "PE6_5") (pintype "input"))
    )
    (net (code "69") (name "/PE7") (class "Default")
      (node (ref "H6") (pin "32") (pinfunction "32_32") (pintype "input"))
      (node (ref "U1") (pin "38") (pinfunction "PE7_38") (pintype "input"))
    )
    (net (code "70") (name "/PE8") (class "Default")
      (node (ref "H6") (pin "31") (pinfunction "31_31") (pintype "input"))
      (node (ref "U1") (pin "39") (pinfunction "PE8_39") (pintype "input"))
    )
    (net (code "71") (name "/PE9") (class "Default")
      (node (ref "H6") (pin "34") (pinfunction "34_34") (pintype "input"))
      (node (ref "U1") (pin "40") (pinfunction "PE9_40") (pintype "input"))
    )
    (net (code "72") (name "/PE10") (class "Default")
      (node (ref "H6") (pin "33") (pinfunction "33_33") (pintype "input"))
      (node (ref "U1") (pin "41") (pinfunction "PE10_41") (pintype "input"))
    )
    (net (code "73") (name "/PE11") (class "Default")
      (node (ref "H6") (pin "36") (pinfunction "36_36") (pintype "input"))
      (node (ref "U1") (pin "42") (pinfunction "PE11_42") (pintype "input"))
    )
    (net (code "74") (name "/PE12") (class "Default")
      (node (ref "H6") (pin "35") (pinfunction "35_35") (pintype "input"))
      (node (ref "U1") (pin "43") (pinfunction "PE12_43") (pintype "input"))
    )
    (net (code "75") (name "/PE13") (class "Default")
      (node (ref "H6") (pin "38") (pinfunction "38_38") (pintype "input"))
      (node (ref "U1") (pin "44") (pinfunction "PE13_44") (pintype "input"))
    )
    (net (code "76") (name "/PE14") (class "Default")
      (node (ref "H6") (pin "37") (pinfunction "37_37") (pintype "input"))
      (node (ref "U1") (pin "45") (pinfunction "PE14_45") (pintype "input"))
    )
    (net (code "77") (name "/PE15") (class "Default")
      (node (ref "H6") (pin "40") (pinfunction "40_40") (pintype "input"))
      (node (ref "U1") (pin "46") (pinfunction "PE15_46") (pintype "input"))
    )
    (net (code "78") (name "/RST") (class "Default")
      (node (ref "C14") (pin "2") (pinfunction "2_2") (pintype "input"))
      (node (ref "R3") (pin "1") (pinfunction "1_1") (pintype "input"))
      (node (ref "SW2") (pin "2") (pinfunction "2_2") (pintype "input"))
      (node (ref "U1") (pin "14") (pinfunction "NRST_14") (pintype "input"))
    )
    (net (code "79") (name "/SWCLK") (class "Default")
      (node (ref "H9") (pin "2") (pinfunction "2_2") (pintype "input"))
      (node (ref "U1") (pin "76") (pinfunction "PA14/SWCLK_76") (pintype "input"))
    )
    (net (code "80") (name "/SWDIO") (class "Default")
      (node (ref "H9") (pin "3") (pinfunction "3_3") (pintype "input"))
      (node (ref "U1") (pin "72") (pinfunction "PA13/SWDIO_72") (pintype "input"))
    )
    (net (code "81") (name "/USB_D+") (class "Default")
      (node (ref "H7") (pin "27") (pinfunction "27_27") (pintype "input"))
      (node (ref "U1") (pin "71") (pinfunction "PA12/USB1DP_71") (pintype "input"))
      (node (ref "USB1") (pin "6") (pinfunction "DP1_6") (pintype "input"))
      (node (ref "USB1") (pin "8") (pinfunction "DP2_8") (pintype "input"))
    )
    (net (code "82") (name "/USB_D-") (class "Default")
      (node (ref "H7") (pin "30") (pinfunction "30_30") (pintype "input"))
      (node (ref "U1") (pin "70") (pinfunction "PA11/USB1DM_70") (pintype "input"))
      (node (ref "USB1") (pin "5") (pinfunction "DN2_5") (pintype "input"))
      (node (ref "USB1") (pin "7") (pinfunction "DN1_7") (pintype "input"))
    )
    (net (code "83") (name "/VBAT") (class "Default")
      (node (ref "C2") (pin "2") (pinfunction "2_2") (pintype "input"))
      (node (ref "H5") (pin "2") (pinfunction "2_2") (pintype "input"))
      (node (ref "U1") (pin "6") (pinfunction "VBAT_6") (pintype "input"))
    )
    (net (code "84") (name "/VDDA") (class "Default")
      (node (ref "C4") (pin "2") (pinfunction "2_2") (pintype "input"))
      (node (ref "H6") (pin "18") (pinfunction "18_18") (pintype "input"))
      (node (ref "R7") (pin "2") (pinfunction "2_2") (pintype "input"))
      (node (ref "U1") (pin "22") (pinfunction "VDDA_22") (pintype "input"))
    )
    (net (code "85") (name "/VREF+") (class "Default")
      (node (ref "C20") (pin "2") (pinfunction "2_2") (pintype "input"))
      (node (ref "H6") (pin "15") (pinfunction "15_15") (pintype "input"))
      (node (ref "R8") (pin "2") (pinfunction "2_2") (pintype "input"))
      (node (ref "R9") (pin "1") (pinfunction "1_1") (pintype "input"))
      (node (ref "U1") (pin "21") (pinfunction "VREF+_21") (pintype "input"))
    )
    (net (code "86") (name "/VREF-") (class "Default")
      (node (ref "H6") (pin "16") (pinfunction "16_16") (pintype "input"))
      (node (ref "R11") (pin "2") (pinfunction "2_2") (pintype "input"))
      (node (ref "U1") (pin "20") (pinfunction "VREF-_20") (pintype "input"))
    )
    (net (code "87") (name "/XIN") (class "Default")
      (node (ref "C13") (pin "2") (pinfunction "2_2") (pintype "input"))
      (node (ref "U1") (pin "8") (pinfunction "PC14/OSC32IN_8") (pintype "input"))
      (node (ref "X2") (pin "1") (pinfunction "OSC1_1") (pintype "input"))
    )
    (net (code "88") (name "/XOUT") (class "Default")
      (node (ref "C15") (pin "2") (pinfunction "2_2") (pintype "input"))
      (node (ref "U1") (pin "9") (pinfunction "PC15/OSC32OUT_9") (pintype "input"))
      (node (ref "X2") (pin "2") (pinfunction "OSC2_2") (pintype "input"))
    )
    (net (code "89") (name "/XT2IN") (class "Default")
      (node (ref "C11") (pin "2") (pinfunction "2_2") (pintype "input"))
      (node (ref "U1") (pin "12") (pinfunction "OSC_IN_12") (pintype "input"))
      (node (ref "X1") (pin "2") (pinfunction "OSC2_2") (pintype "input"))
    )
    (net (code "90") (name "/XT2OUT") (class "Default")
      (node (ref "C12") (pin "2") (pinfunction "2_2") (pintype "input"))
      (node (ref "U1") (pin "13") (pinfunction "OSC_OUT_13") (pintype "input"))
      (node (ref "X1") (pin "1") (pinfunction "OSC1_1") (pintype "input"))
    )
    (net (code "91") (name "1.25V") (class "Default")
      (node (ref "H8") (pin "1") (pinfunction "1_1") (pintype "input"))
      (node (ref "R5") (pin "1") (pinfunction "1_1") (pintype "input"))
      (node (ref "R6") (pin "2") (pinfunction "2_2") (pintype "input"))
      (node (ref "U3") (pin "1") (pinfunction "REF_1") (pintype "input"))
    )
    (net (code "92") (name "3.29V") (class "Default")
      (node (ref "C18") (pin "2") (pinfunction "2_2") (pintype "input"))
      (node (ref "R4") (pin "2") (pinfunction "2_2") (pintype "input"))
      (node (ref "R5") (pin "2") (pinfunction "2_2") (pintype "input"))
      (node (ref "R9") (pin "2") (pinfunction "2_2") (pintype "input"))
      (node (ref "U3") (pin "2") (pinfunction "Cathode_2") (pintype "input"))
    )
    (net (code "93") (name "GND") (class "Default")
      (node (ref "B1") (pin "2") (pinfunction "2_2") (pintype "input"))
      (node (ref "C1") (pin "1") (pinfunction "1_1") (pintype "input"))
      (node (ref "C10") (pin "1") (pinfunction "1_1") (pintype "input"))
      (node (ref "C11") (pin "1") (pinfunction "1_1") (pintype "input"))
      (node (ref "C12") (pin "1") (pinfunction "1_1") (pintype "input"))
      (node (ref "C13") (pin "1") (pinfunction "1_1") (pintype "input"))
      (node (ref "C14") (pin "1") (pinfunction "1_1") (pintype "input"))
      (node (ref "C15") (pin "1") (pinfunction "1_1") (pintype "input"))
      (node (ref "C16") (pin "1") (pinfunction "1_1") (pintype "input"))
      (node (ref "C17") (pin "1") (pinfunction "1_1") (pintype "input"))
      (node (ref "C18") (pin "1") (pinfunction "1_1") (pintype "input"))
      (node (ref "C19") (pin "1") (pinfunction "1_1") (pintype "input"))
      (node (ref "C2") (pin "1") (pinfunction "1_1") (pintype "input"))
      (node (ref "C20") (pin "1") (pinfunction "1_1") (pintype "input"))
      (node (ref "C21") (pin "1") (pinfunction "1_1") (pintype "input"))
      (node (ref "C3") (pin "1") (pinfunction "1_1") (pintype "input"))
      (node (ref "C4") (pin "1") (pinfunction "1_1") (pintype "input"))
      (node (ref "C5") (pin "2") (pinfunction "2_2") (pintype "input"))
      (node (ref "C6") (pin "1") (pinfunction "1_1") (pintype "input"))
      (node (ref "C7") (pin "2") (pinfunction "2_2") (pintype "input"))
      (node (ref "C8") (pin "1") (pinfunction "1_1") (pintype "input"))
      (node (ref "C9") (pin "1") (pinfunction "1_1") (pintype "input"))
      (node (ref "H6") (pin "3") (pinfunction "3_3") (pintype "input"))
      (node (ref "H6") (pin "4") (pinfunction "4_4") (pintype "input"))
      (node (ref "H6") (pin "47") (pinfunction "47_47") (pintype "input"))
      (node (ref "H6") (pin "48") (pinfunction "48_48") (pintype "input"))
      (node (ref "H6") (pin "49") (pinfunction "49_49") (pintype "input"))
      (node (ref "H6") (pin "50") (pinfunction "50_50") (pintype "input"))
      (node (ref "H7") (pin "3") (pinfunction "3_3") (pintype "input"))
      (node (ref "H7") (pin "4") (pinfunction "4_4") (pintype "input"))
      (node (ref "H7") (pin "50") (pinfunction "50_50") (pintype "input"))
      (node (ref "H9") (pin "1") (pinfunction "1_1") (pintype "input"))
      (node (ref "LED1") (pin "1") (pinfunction "C_1") (pintype "input"))
      (node (ref "R1") (pin "2") (pinfunction "2_2") (pintype "input"))
      (node (ref "R11") (pin "1") (pinfunction "1_1") (pintype "input"))
      (node (ref "R13") (pin "1") (pinfunction "1_1") (pintype "input"))
      (node (ref "R14") (pin "1") (pinfunction "1_1") (pintype "input"))
      (node (ref "R18") (pin "2") (pinfunction "2_2") (pintype "input"))
      (node (ref "R6") (pin "1") (pinfunction "1_1") (pintype "input"))
      (node (ref "SW2") (pin "1") (pinfunction "1_1") (pintype "input"))
      (node (ref "SW4") (pin "1") (pinfunction "1_1") (pintype "input"))
      (node (ref "SW5") (pin "1") (pinfunction "1_1") (pintype "input"))
      (node (ref "SW6") (pin "1") (pinfunction "1_1") (pintype "input"))
      (node (ref "U1") (pin "10") (pinfunction "VSS_5_10") (pintype "input"))
      (node (ref "U1") (pin "19") (pinfunction "VSSA_19") (pintype "input"))
      (node (ref "U1") (pin "27") (pinfunction "VSS_4_27") (pintype "input"))
      (node (ref "U1") (pin "49") (pinfunction "VSS_1_49") (pintype "input"))
      (node (ref "U1") (pin "74") (pinfunction "VSS_2_74") (pintype "input"))
      (node (ref "U1") (pin "99") (pinfunction "VSS_3_99") (pintype "input"))
      (node (ref "U2") (pin "1") (pinfunction "ADJ(GND)_1") (pintype "input"))
      (node (ref "U3") (pin "3") (pinfunction "Anode_3") (pintype "input"))
      (node (ref "U4") (pin "4") (pinfunction "GND_4") (pintype "input"))
      (node (ref "USB1") (pin "1") (pinfunction "GND_1") (pintype "input"))
      (node (ref "USB1") (pin "12") (pinfunction "GND_12") (pintype "input"))
      (node (ref "USB1") (pin "13") (pinfunction "SHELL_13") (pintype "input"))
      (node (ref "USB1") (pin "14") (pinfunction "SHELL_14") (pintype "input"))
    )
    (net (code "94") (name "Net-(B1-Pad1)") (class "Default")
      (node (ref "B1") (pin "1") (pinfunction "1_1") (pintype "input"))
      (node (ref "H5") (pin "3") (pinfunction "3_3") (pintype "input"))
    )
    (net (code "95") (name "Net-(LED1-A)") (class "Default")
      (node (ref "LED1") (pin "2") (pinfunction "A_2") (pintype "input"))
      (node (ref "R2") (pin "2") (pinfunction "2_2") (pintype "input"))
    )
    (net (code "96") (name "Net-(LED2-A)") (class "Default")
      (node (ref "LED2") (pin "2") (pinfunction "A_2") (pintype "input"))
      (node (ref "R15") (pin "2") (pinfunction "2_2") (pintype "input"))
    )
    (net (code "97") (name "Net-(LED3-A)") (class "Default")
      (node (ref "LED3") (pin "2") (pinfunction "A_2") (pintype "input"))
      (node (ref "R16") (pin "2") (pinfunction "2_2") (pintype "input"))
    )
    (net (code "98") (name "Net-(LED4-A)") (class "Default")
      (node (ref "LED4") (pin "2") (pinfunction "A_2") (pintype "input"))
      (node (ref "R17") (pin "2") (pinfunction "2_2") (pintype "input"))
    )
    (net (code "99") (name "Net-(USB1-CC1)") (class "Default")
      (node (ref "R18") (pin "1") (pinfunction "1_1") (pintype "input"))
      (node (ref "USB1") (pin "4") (pinfunction "CC1_4") (pintype "input"))
    )
    (net (code "100") (name "Net-(USB1-CC2)") (class "Default")
      (node (ref "R1") (pin "1") (pinfunction "1_1") (pintype "input"))
      (node (ref "USB1") (pin "10") (pinfunction "CC2_10") (pintype "input"))
    )
    (net (code "101") (name "VIN") (class "Default")
      (node (ref "SW1") (pin "2") (pinfunction "2_2") (pintype "input"))
      (node (ref "SW1") (pin "5") (pinfunction "5_5") (pintype "input"))
      (node (ref "USB1") (pin "11") (pinfunction "VBUS_11") (pintype "input"))
      (node (ref "USB1") (pin "2") (pinfunction "VBUS_2") (pintype "input"))
    )
    (net (code "102") (name "unconnected-(SW1-Pad1)") (class "Default")
      (node (ref "SW1") (pin "1") (pinfunction "1_1") (pintype "input"))
    )
    (net (code "103") (name "unconnected-(SW1-Pad4)") (class "Default")
      (node (ref "SW1") (pin "4") (pinfunction "4_4") (pintype "input"))
    )
    (net (code "104") (name "unconnected-(TP1-Pad1)") (class "Default")
      (node (ref "TP1") (pin "1") (pinfunction "1_1") (pintype "input"))
    )
    (net (code "105") (name "unconnected-(TP2-Pad1)") (class "Default")
      (node (ref "TP2") (pin "1") (pinfunction "1_1") (pintype "input"))
    )
    (net (code "106") (name "unconnected-(TP3-Pad1)") (class "Default")
      (node (ref "TP3") (pin "1") (pinfunction "1_1") (pintype "input"))
    )
    (net (code "107") (name "unconnected-(TP4-Pad1)") (class "Default")
      (node (ref "TP4") (pin "1") (pinfunction "1_1") (pintype "input"))
    )
    (net (code "108") (name "unconnected-(U1-NC-Pad73)") (class "Default")
      (node (ref "U1") (pin "73") (pinfunction "NC_73") (pintype "input+no_connect"))
    )
    (net (code "109") (name "unconnected-(USB1-SBU1-Pad9)") (class "Default")
      (node (ref "USB1") (pin "9") (pinfunction "SBU1_9") (pintype "input"))
    )
    (net (code "110") (name "unconnected-(USB1-SBU2-Pad3)") (class "Default")
      (node (ref "USB1") (pin "3") (pinfunction "SBU2_3") (pintype "input"))
    )
  )
)
